# 7SD_1_1.net
KiCad netlist of a schematic drawn in EAGLE
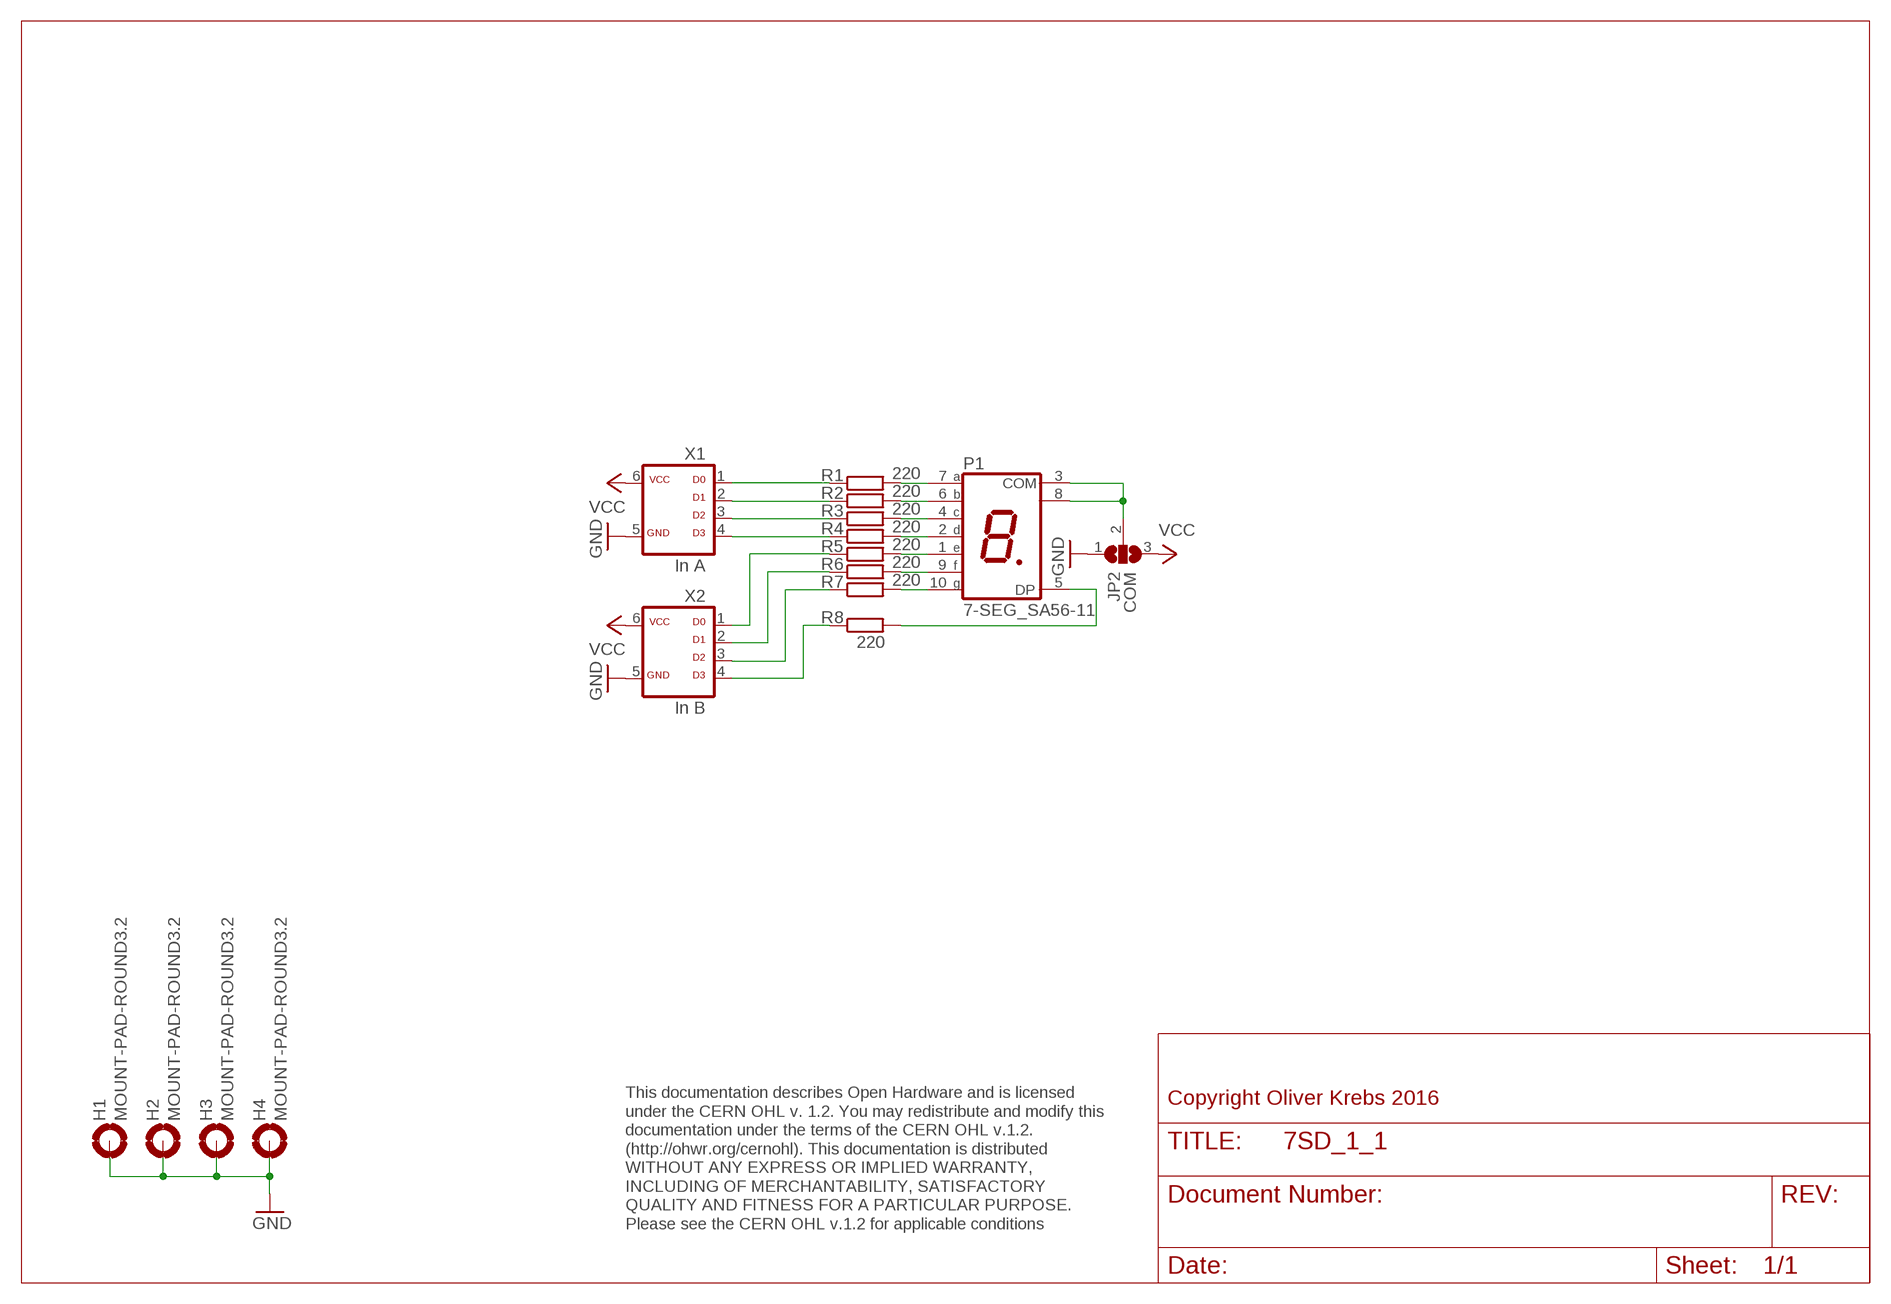
[diagram p0: schematic, sheet 1]

(export (version "E")
  (design (tool "Eeschema 10.0.6"))
  (components
    (comp (ref "H1")
      (value "MOUNT-PAD-ROUND3.2")
      (footprint "eagle-import:3,2-PAD")
      (libsource (lib "eagle-import") (part "MOUNT-PAD-ROUND3.2"))
    )
    (comp (ref "H2")
      (value "MOUNT-PAD-ROUND3.2")
      (footprint "eagle-import:3,2-PAD")
      (libsource (lib "eagle-import") (part "MOUNT-PAD-ROUND3.2"))
    )
    (comp (ref "H3")
      (value "MOUNT-PAD-ROUND3.2")
      (footprint "eagle-import:3,2-PAD")
      (libsource (lib "eagle-import") (part "MOUNT-PAD-ROUND3.2"))
    )
    (comp (ref "H4")
      (value "MOUNT-PAD-ROUND3.2")
      (footprint "eagle-import:3,2-PAD")
      (libsource (lib "eagle-import") (part "MOUNT-PAD-ROUND3.2"))
    )
    (comp (ref "JP2")
      (value "COM")
      (footprint "eagle-import:SJ_2")
      (libsource (lib "eagle-import") (part "SJ2W"))
    )
    (comp (ref "P1")
      (value "7-SEG_SA56-11")
      (footprint "eagle-import:SA56-11")
      (libsource (lib "eagle-import") (part "7-SEG_SA56-11"))
    )
    (comp (ref "R1")
      (value "220")
      (footprint "eagle-import:0207_10")
      (libsource (lib "eagle-import") (part "R-EU_0207/10"))
    )
    (comp (ref "R2")
      (value "220")
      (footprint "eagle-import:0207_10")
      (libsource (lib "eagle-import") (part "R-EU_0207/10"))
    )
    (comp (ref "R3")
      (value "220")
      (footprint "eagle-import:0207_10")
      (libsource (lib "eagle-import") (part "R-EU_0207/10"))
    )
    (comp (ref "R4")
      (value "220")
      (footprint "eagle-import:0207_10")
      (libsource (lib "eagle-import") (part "R-EU_0207/10"))
    )
    (comp (ref "R5")
      (value "220")
      (footprint "eagle-import:0207_10")
      (libsource (lib "eagle-import") (part "R-EU_0207/10"))
    )
    (comp (ref "R6")
      (value "220")
      (footprint "eagle-import:0207_10")
      (libsource (lib "eagle-import") (part "R-EU_0207/10"))
    )
    (comp (ref "R7")
      (value "220")
      (footprint "eagle-import:0207_10")
      (libsource (lib "eagle-import") (part "R-EU_0207/10"))
    )
    (comp (ref "R8")
      (value "220")
      (footprint "eagle-import:0207_10")
      (libsource (lib "eagle-import") (part "R-EU_0207/10"))
    )
    (comp (ref "X1")
      (value "In A")
      (footprint "eagle-import:ML-6")
      (libsource (lib "eagle-import") (part "ML6D"))
    )
    (comp (ref "X2")
      (value "In B")
      (footprint "eagle-import:ML-6")
      (libsource (lib "eagle-import") (part "ML6D"))
    )
  )
  (nets
    (net (code "1") (name "GND") (class "Default")
      (node (ref "H1") (pin "B3,2") (pinfunction "MOUNT_B3,2") (pintype "passive"))
      (node (ref "H2") (pin "B3,2") (pinfunction "MOUNT_B3,2") (pintype "passive"))
      (node (ref "H3") (pin "B3,2") (pinfunction "MOUNT_B3,2") (pintype "passive"))
      (node (ref "H4") (pin "B3,2") (pinfunction "MOUNT_B3,2") (pintype "passive"))
      (node (ref "JP2") (pin "1") (pinfunction "1_1") (pintype "passive"))
      (node (ref "X1") (pin "5") (pinfunction "5_5") (pintype "passive"))
      (node (ref "X2") (pin "5") (pinfunction "5_5") (pintype "passive"))
    )
    (net (code "2") (name "Net-(JP2-Pad2)") (class "Default")
      (node (ref "JP2") (pin "2") (pinfunction "2_2") (pintype "passive"))
      (node (ref "P1") (pin "3") (pinfunction "COM_3") (pintype "passive"))
      (node (ref "P1") (pin "8") (pinfunction "COM_8") (pintype "passive"))
    )
    (net (code "3") (name "Net-(P1-A)") (class "Default")
      (node (ref "P1") (pin "7") (pinfunction "A_7") (pintype "passive"))
      (node (ref "R1") (pin "2") (pinfunction "2_2") (pintype "passive"))
    )
    (net (code "4") (name "Net-(P1-B)") (class "Default")
      (node (ref "P1") (pin "6") (pinfunction "B_6") (pintype "passive"))
      (node (ref "R2") (pin "2") (pinfunction "2_2") (pintype "passive"))
    )
    (net (code "5") (name "Net-(P1-C)") (class "Default")
      (node (ref "P1") (pin "4") (pinfunction "C_4") (pintype "passive"))
      (node (ref "R3") (pin "2") (pinfunction "2_2") (pintype "passive"))
    )
    (net (code "6") (name "Net-(P1-D)") (class "Default")
      (node (ref "P1") (pin "2") (pinfunction "D_2") (pintype "passive"))
      (node (ref "R4") (pin "2") (pinfunction "2_2") (pintype "passive"))
    )
    (net (code "7") (name "Net-(P1-DP)") (class "Default")
      (node (ref "P1") (pin "5") (pinfunction "DP_5") (pintype "passive"))
      (node (ref "R8") (pin "2") (pinfunction "2_2") (pintype "passive"))
    )
    (net (code "8") (name "Net-(P1-E)") (class "Default")
      (node (ref "P1") (pin "1") (pinfunction "E_1") (pintype "passive"))
      (node (ref "R5") (pin "2") (pinfunction "2_2") (pintype "passive"))
    )
    (net (code "9") (name "Net-(P1-F)") (class "Default")
      (node (ref "P1") (pin "9") (pinfunction "F_9") (pintype "passive"))
      (node (ref "R6") (pin "2") (pinfunction "2_2") (pintype "passive"))
    )
    (net (code "10") (name "Net-(P1-G)") (class "Default")
      (node (ref "P1") (pin "10") (pinfunction "G_10") (pintype "passive"))
      (node (ref "R7") (pin "2") (pinfunction "2_2") (pintype "passive"))
    )
    (net (code "11") (name "Net-(R1-Pad1)") (class "Default")
      (node (ref "R1") (pin "1") (pinfunction "1_1") (pintype "passive"))
      (node (ref "X1") (pin "1") (pinfunction "1_1") (pintype "passive"))
    )
    (net (code "12") (name "Net-(R2-Pad1)") (class "Default")
      (node (ref "R2") (pin "1") (pinfunction "1_1") (pintype "passive"))
      (node (ref "X1") (pin "2") (pinfunction "2_2") (pintype "passive"))
    )
    (net (code "13") (name "Net-(R3-Pad1)") (class "Default")
      (node (ref "R3") (pin "1") (pinfunction "1_1") (pintype "passive"))
      (node (ref "X1") (pin "3") (pinfunction "3_3") (pintype "passive"))
    )
    (net (code "14") (name "Net-(R4-Pad1)") (class "Default")
      (node (ref "R4") (pin "1") (pinfunction "1_1") (pintype "passive"))
      (node (ref "X1") (pin "4") (pinfunction "4_4") (pintype "passive"))
    )
    (net (code "15") (name "Net-(R5-Pad1)") (class "Default")
      (node (ref "R5") (pin "1") (pinfunction "1_1") (pintype "passive"))
      (node (ref "X2") (pin "1") (pinfunction "1_1") (pintype "passive"))
    )
    (net (code "16") (name "Net-(R6-Pad1)") (class "Default")
      (node (ref "R6") (pin "1") (pinfunction "1_1") (pintype "passive"))
      (node (ref "X2") (pin "2") (pinfunction "2_2") (pintype "passive"))
    )
    (net (code "17") (name "Net-(R7-Pad1)") (class "Default")
      (node (ref "R7") (pin "1") (pinfunction "1_1") (pintype "passive"))
      (node (ref "X2") (pin "3") (pinfunction "3_3") (pintype "passive"))
    )
    (net (code "18") (name "Net-(R8-Pad1)") (class "Default")
      (node (ref "R8") (pin "1") (pinfunction "1_1") (pintype "passive"))
      (node (ref "X2") (pin "4") (pinfunction "4_4") (pintype "passive"))
    )
    (net (code "19") (name "VCC") (class "Default")
      (node (ref "JP2") (pin "3") (pinfunction "3_3") (pintype "passive"))
      (node (ref "X1") (pin "6") (pinfunction "6_6") (pintype "passive"))
      (node (ref "X2") (pin "6") (pinfunction "6_6") (pintype "passive"))
    )
  )
)
